# Estimador.net
KiCad netlist of a schematic drawn in Altium Designer
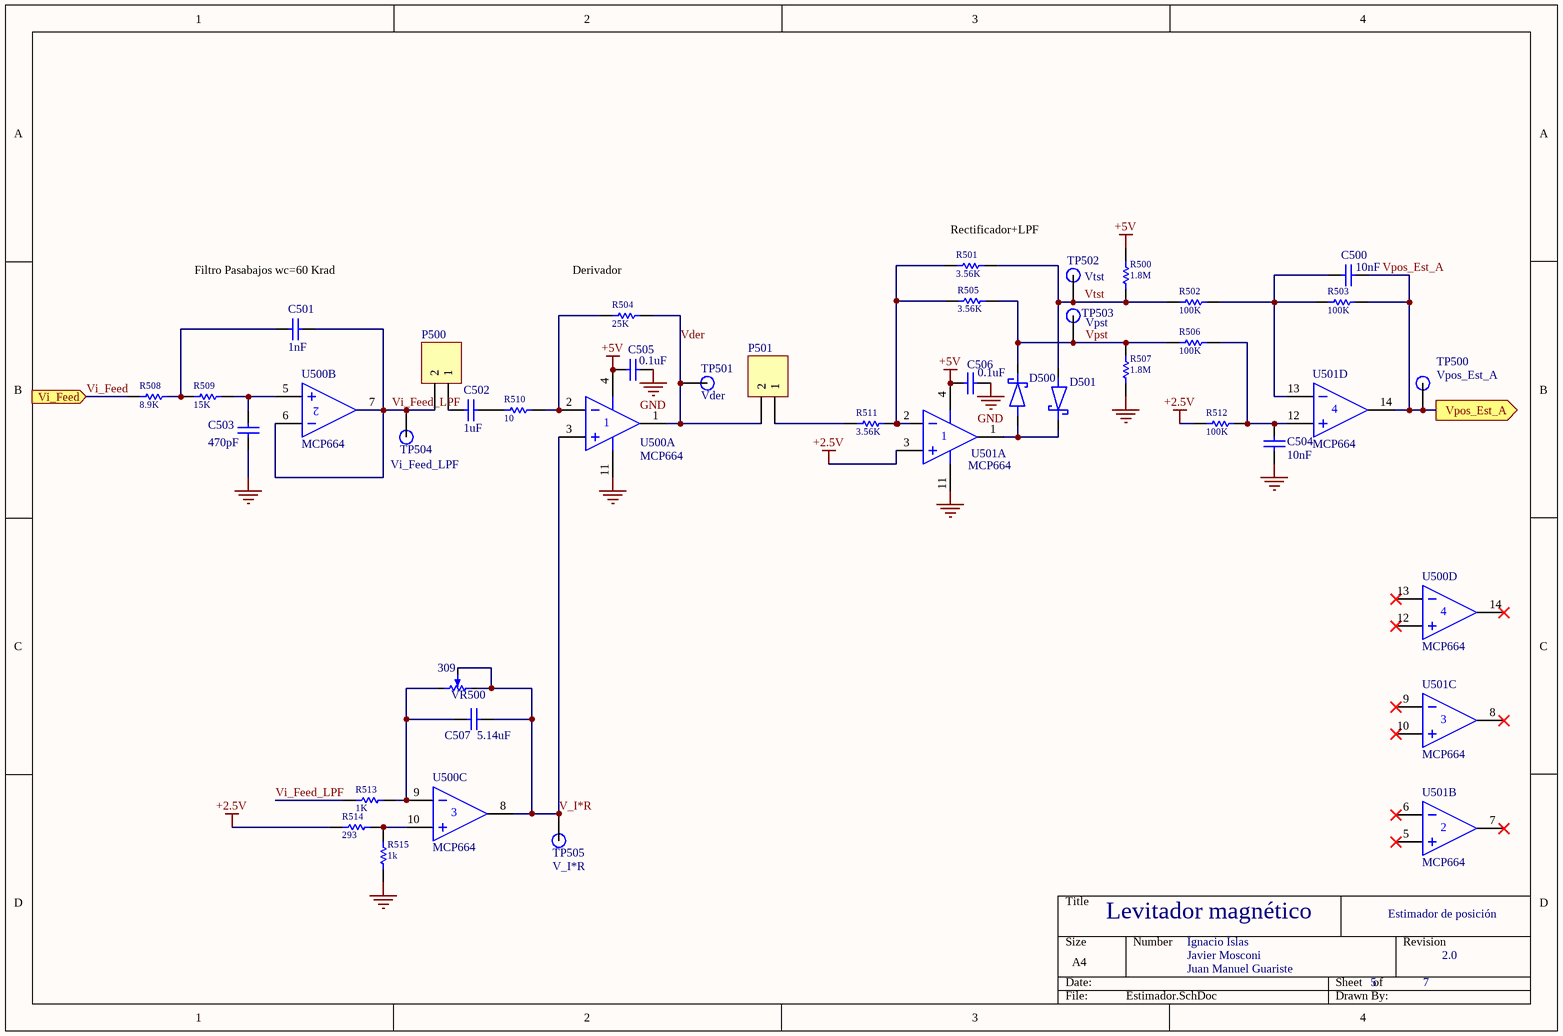
[diagram p0: Estimador.SchDoc]

(export (version "E")
  (design (tool "Eeschema 10.0.6"))
  (components
    (comp (ref "C500")
      (value "10nF")
      (footprint "C1206")
      (description "CAP CER 10000PF 500V X7R 1206")
      (fields (field (name "MANUFACTURER") "KEMET") (field (name "Comment") "Capacitor"))
      (libsource (lib "Levitador_GMI") (part "Capacitor"))
    )
    (comp (ref "C501")
      (value "1nF")
      (footprint "C1206")
      (description "CAP CER 1000PF 2KV X7R 1206")
      (fields (field (name "MANUFACTURER") "Johanson Dielectrics Inc.") (field (name "Comment") "Capacitor"))
      (libsource (lib "Levitador_GMI") (part "Capacitor"))
    )
    (comp (ref "C502")
      (value "1uF")
      (footprint "C1206")
      (description "CAP CER 1UF 25V X7R 1206")
      (fields (field (name "MANUFACTURER") "CAL-CHIP ELECTRONICS, INC.") (field (name "Comment") "Capacitor"))
      (libsource (lib "Levitador_GMI") (part "Capacitor"))
    )
    (comp (ref "C503")
      (value "470pF")
      (footprint "C1206")
      (description "CAP CER 470PF 1KV C0G/NP0 1206")
      (fields (field (name "MANUFACTURER") "Samsung Electro-Mechanics") (field (name "Comment") "Capacitor"))
      (libsource (lib "Levitador_GMI") (part "Capacitor"))
    )
    (comp (ref "C504")
      (value "10nF")
      (footprint "C1206")
      (description "CAP CER 10000PF 500V X7R 1206")
      (fields (field (name "MANUFACTURER") "KEMET") (field (name "Comment") "Capacitor"))
      (libsource (lib "Levitador_GMI") (part "Capacitor"))
    )
    (comp (ref "C505")
      (value "0.1uF")
      (footprint "C1206")
      (description "CAP CER 0.1UF 50V X7R 1206")
      (fields (field (name "MANUFACTURER") "Venkel") (field (name "Comment") "Capacitor"))
      (libsource (lib "Levitador_GMI") (part "Capacitor"))
    )
    (comp (ref "C506")
      (value "0.1uF")
      (footprint "C1206")
      (description "CAP CER 0.1UF 50V X7R 1206")
      (fields (field (name "MANUFACTURER") "Venkel") (field (name "Comment") "Capacitor"))
      (libsource (lib "Levitador_GMI") (part "Capacitor"))
    )
    (comp (ref "C507")
      (value "5.14uF")
      (footprint "C1206")
      (description "CAP CER 5100PF 100V NP0 5% 1206")
      (fields (field (name "MANUFACTURER") "KEMET") (field (name "Comment") "Capacitor"))
      (libsource (lib "Levitador_GMI") (part "Capacitor"))
    )
    (comp (ref "D500")
      (value "RSX205LAM30TR")
      (footprint "SODFL4725X105N")
      (description "DIODE SCHOTTKY 30V 2A PMDTM")
      (fields (field (name "MANUFACTURER") "ROHM Semiconductor"))
      (libsource (lib "Levitador_GMI") (part "RSX205LAM30TR"))
    )
    (comp (ref "D501")
      (value "RSX205LAM30TR")
      (footprint "SODFL4725X105N")
      (description "DIODE SCHOTTKY 30V 2A PMDTM")
      (fields (field (name "MANUFACTURER") "ROHM Semiconductor"))
      (libsource (lib "Levitador_GMI") (part "RSX205LAM30TR"))
    )
    (comp (ref "P500")
      (value "Header 2")
      (footprint "HDR1X2")
      (description "TERM BLK 2P SIDE ENT 2.54MM PCB")
      (fields (field (name "MANUFACTURER") "TE Connectivity AMP Connectors"))
      (libsource (lib "Levitador_GMI") (part "Header 2"))
    )
    (comp (ref "P501")
      (value "Header 2")
      (footprint "HDR1X2")
      (description "TERM BLK 2P SIDE ENT 2.54MM PCB")
      (fields (field (name "MANUFACTURER") "TE Connectivity AMP Connectors"))
      (libsource (lib "Levitador_GMI") (part "Header 2"))
    )
    (comp (ref "R500")
      (value "1.8M")
      (footprint "Levitador_GMI:R1206")
      (description "RES 1.8M OHM 1% 1/4W 1206")
      (fields (field (name "MANUFACTURER") "YAGEO") (field (name "TOLERANCE") "1%"))
      (libsource (lib "Levitador_GMI") (part "R1206"))
    )
    (comp (ref "R501")
      (value "3.56K")
      (footprint "Levitador_GMI:R1206")
      (description "RES 3.57K OHM 1% 1/4W 1206")
      (fields (field (name "MANUFACTURER") "YAGEO") (field (name "TOLERANCE") "1%"))
      (libsource (lib "Levitador_GMI") (part "R1206"))
    )
    (comp (ref "R502")
      (value "100K")
      (footprint "Levitador_GMI:R1206")
      (description "RES 100K OHM 1% 1/4W 1206")
      (fields (field (name "MANUFACTURER") "Stackpole Electronics Inc") (field (name "TOLERANCE") "1%"))
      (libsource (lib "Levitador_GMI") (part "R1206"))
    )
    (comp (ref "R503")
      (value "100K")
      (footprint "Levitador_GMI:R1206")
      (description "RES 100K OHM 1% 1/4W 1206")
      (fields (field (name "MANUFACTURER") "Stackpole Electronics Inc") (field (name "TOLERANCE") "1%"))
      (libsource (lib "Levitador_GMI") (part "R1206"))
    )
    (comp (ref "R504")
      (value "25K")
      (footprint "Levitador_GMI:R1206")
      (description "RES SMD 25K OHM 1% 1/4W 1206")
      (fields
        (field (name "MANUFACTURER") "Vishay Foil Resistors (Division of Vishay Precision Group)")
        (field (name "TOLERANCE") "1%")
      )
      (libsource (lib "Levitador_GMI") (part "R1206"))
    )
    (comp (ref "R505")
      (value "3.56K")
      (footprint "Levitador_GMI:R1206")
      (description "RES 3.57K OHM 1% 1/4W 1206")
      (fields (field (name "MANUFACTURER") "YAGEO") (field (name "TOLERANCE") "1%"))
      (libsource (lib "Levitador_GMI") (part "R1206"))
    )
    (comp (ref "R506")
      (value "100K")
      (footprint "Levitador_GMI:R1206")
      (description "RES 100K OHM 1% 1/4W 1206")
      (fields (field (name "MANUFACTURER") "Stackpole Electronics Inc") (field (name "TOLERANCE") "1%"))
      (libsource (lib "Levitador_GMI") (part "R1206"))
    )
    (comp (ref "R507")
      (value "1.8M")
      (footprint "Levitador_GMI:R1206")
      (description "RES 1.8M OHM 1% 1/4W 1206")
      (fields (field (name "MANUFACTURER") "YAGEO") (field (name "TOLERANCE") "1%"))
      (libsource (lib "Levitador_GMI") (part "R1206"))
    )
    (comp (ref "R508")
      (value "8.9K")
      (footprint "Levitador_GMI:R1206")
      (description "RES 8.87K OHM 1% 1/4W 1206")
      (fields (field (name "MANUFACTURER") "YAGEO") (field (name "TOLERANCE") "1%"))
      (libsource (lib "Levitador_GMI") (part "R1206"))
    )
    (comp (ref "R509")
      (value "15K")
      (footprint "Levitador_GMI:R1206")
      (description "RES 15K OHM 1% 1/4W 1206")
      (fields (field (name "MANUFACTURER") "Vishay Dale") (field (name "TOLERANCE") "1%"))
      (libsource (lib "Levitador_GMI") (part "R1206"))
    )
    (comp (ref "R510")
      (value "10")
      (footprint "Levitador_GMI:R1206")
      (description "RES 10 OHM 1% 1/4W 1206")
      (fields (field (name "MANUFACTURER") "Stackpole Electronics Inc") (field (name "TOLERANCE") "1%"))
      (libsource (lib "Levitador_GMI") (part "R1206"))
    )
    (comp (ref "R511")
      (value "3.56K")
      (footprint "Levitador_GMI:R1206")
      (description "RES 3.57K OHM 1% 1/4W 1206")
      (fields (field (name "MANUFACTURER") "YAGEO") (field (name "TOLERANCE") "1%"))
      (libsource (lib "Levitador_GMI") (part "R1206"))
    )
    (comp (ref "R512")
      (value "100K")
      (footprint "Levitador_GMI:R1206")
      (description "RES 100K OHM 1% 1/4W 1206")
      (fields (field (name "MANUFACTURER") "Stackpole Electronics Inc") (field (name "TOLERANCE") "1%"))
      (libsource (lib "Levitador_GMI") (part "R1206"))
    )
    (comp (ref "R513")
      (value "1K")
      (footprint "Levitador_GMI:R1206")
      (description "RES 1K OHM 1% 1/4W 1206")
      (fields (field (name "MANUFACTURER") "Stackpole Electronics Inc") (field (name "TOLERANCE") "1%"))
      (libsource (lib "Levitador_GMI") (part "R1206"))
    )
    (comp (ref "R514")
      (value "293")
      (footprint "Levitador_GMI:R1206")
      (description "RES SMD 294 OHM 1% 1/4W 1206")
      (fields (field (name "MANUFACTURER") "Vishay Dale") (field (name "TOLERANCE") "1%"))
      (libsource (lib "Levitador_GMI") (part "R1206"))
    )
    (comp (ref "R515")
      (value "1k")
      (footprint "Levitador_GMI:R1206")
      (description "RES 1K OHM 1% 1/4W 1206")
      (fields (field (name "MANUFACTURER") "Stackpole Electronics Inc") (field (name "TOLERANCE") "1%"))
      (libsource (lib "Levitador_GMI") (part "R1206"))
    )
    (comp (ref "TP500")
      (value "Vpos_Est_A")
      (footprint "TestPoint Keystone 5000 Silver-Red")
      (description "PC TEST POINT MINIATURE RED")
      (fields (field (name "MANUFACTURER") "Keystone Electronics"))
      (libsource (lib "Levitador_GMI") (part "Testpoint"))
    )
    (comp (ref "TP501")
      (value "Vder")
      (footprint "TestPoint Keystone 5000 Silver-Red")
      (description "PC TEST POINT MINIATURE RED")
      (fields (field (name "MANUFACTURER") "Keystone Electronics"))
      (libsource (lib "Levitador_GMI") (part "Testpoint"))
    )
    (comp (ref "TP502")
      (value "Vtst")
      (footprint "TestPoint Keystone 5000 Silver-Red")
      (description "PC TEST POINT MINIATURE RED")
      (fields (field (name "MANUFACTURER") "Keystone Electronics"))
      (libsource (lib "Levitador_GMI") (part "Testpoint"))
    )
    (comp (ref "TP503")
      (value "Vpst")
      (footprint "TestPoint Keystone 5000 Silver-Red")
      (description "PC TEST POINT MINIATURE RED")
      (fields (field (name "MANUFACTURER") "Keystone Electronics"))
      (libsource (lib "Levitador_GMI") (part "Testpoint"))
    )
    (comp (ref "TP504")
      (value "Vi_Feed_LPF")
      (footprint "TestPoint Keystone 5000 Silver-Red")
      (description "PC TEST POINT MINIATURE RED")
      (fields (field (name "MANUFACTURER") "Keystone Electronics"))
      (libsource (lib "Levitador_GMI") (part "Testpoint"))
    )
    (comp (ref "TP505")
      (value "V_I*R")
      (footprint "TestPoint Keystone 5000 Silver-Red")
      (description "PC TEST POINT MINIATURE RED")
      (fields (field (name "MANUFACTURER") "Keystone Electronics"))
      (libsource (lib "Levitador_GMI") (part "Testpoint"))
    )
    (comp (ref "U500")
      (value "MCP664")
      (footprint "SOIC14")
      (description "IC OPAMP GP 4 CIRCUIT 14TSSOP")
      (fields (field (name "MANUFACTURER") "Microchip Technology"))
      (libsource (lib "Levitador_GMI") (part "MCP664"))
    )
    (comp (ref "U501")
      (value "MCP664")
      (footprint "SOIC14")
      (description "IC OPAMP GP 4 CIRCUIT 14TSSOP")
      (fields (field (name "MANUFACTURER") "Microchip Technology"))
      (libsource (lib "Levitador_GMI") (part "MCP664"))
    )
    (comp (ref "VR500")
      (value "309")
      (footprint "3299Y1203LF")
      (description "TRIMMER 500 OHM 0.5W PC PIN TOP")
      (fields (field (name "MANUFACTURER") "Bourns Inc.") (field (name "Comment") "Trimmer (Thru-Hole)"))
      (libsource (lib "Levitador_GMI") (part "Trimmer"))
    )
  )
  (nets
    (net (code "1") (name "+2.5V") (class "Default")
      (node (ref "R512") (pin "2") (pinfunction "2_2") (pintype "passive"))
      (node (ref "R514") (pin "1") (pinfunction "1_1") (pintype "passive"))
      (node (ref "U501") (pin "3") (pinfunction "IN+_3") (pintype "passive"))
    )
    (net (code "2") (name "+5V") (class "Default")
      (node (ref "C505") (pin "1") (pinfunction "1_1") (pintype "passive"))
      (node (ref "C506") (pin "1") (pinfunction "1_1") (pintype "passive"))
      (node (ref "R500") (pin "2") (pinfunction "2_2") (pintype "passive"))
      (node (ref "U500") (pin "4") (pinfunction "V+_4") (pintype "power_in"))
      (node (ref "U501") (pin "4") (pinfunction "V+_4") (pintype "power_in"))
    )
    (net (code "3") (name "/V_I*R") (class "Default")
      (node (ref "C507") (pin "1") (pinfunction "1_1") (pintype "passive"))
      (node (ref "TP505") (pin "1") (pinfunction "1_1") (pintype "passive"))
      (node (ref "U500") (pin "3") (pinfunction "IN+_3") (pintype "passive"))
      (node (ref "U500") (pin "8") (pinfunction "OUT_8") (pintype "passive"))
      (node (ref "VR500") (pin "2") (pinfunction "W_2") (pintype "passive"))
      (node (ref "VR500") (pin "3") (pinfunction "CW_3") (pintype "passive"))
    )
    (net (code "4") (name "/Vder") (class "Default")
      (node (ref "P501") (pin "2") (pinfunction "2_2") (pintype "passive"))
      (node (ref "R504") (pin "2") (pinfunction "2_2") (pintype "passive"))
      (node (ref "TP501") (pin "1") (pinfunction "1_1") (pintype "passive"))
      (node (ref "U500") (pin "1") (pinfunction "OUT_1") (pintype "passive"))
    )
    (net (code "5") (name "/Vi_Feed") (class "Default")
      (node (ref "R508") (pin "1") (pinfunction "1_1") (pintype "passive"))
    )
    (net (code "6") (name "/Vi_Feed_LPF") (class "Default")
      (node (ref "C501") (pin "1") (pinfunction "1_1") (pintype "passive"))
      (node (ref "P500") (pin "2") (pinfunction "2_2") (pintype "passive"))
      (node (ref "R513") (pin "1") (pinfunction "1_1") (pintype "passive"))
      (node (ref "TP504") (pin "1") (pinfunction "1_1") (pintype "passive"))
      (node (ref "U500") (pin "6") (pinfunction "IN-_6") (pintype "passive"))
      (node (ref "U500") (pin "7") (pinfunction "OUT_7") (pintype "passive"))
    )
    (net (code "7") (name "/Vpos_Est_A") (class "Default")
      (node (ref "C500") (pin "1") (pinfunction "1_1") (pintype "passive"))
      (node (ref "R503") (pin "1") (pinfunction "1_1") (pintype "passive"))
      (node (ref "TP500") (pin "1") (pinfunction "1_1") (pintype "passive"))
      (node (ref "U501") (pin "14") (pinfunction "OUT_14") (pintype "passive"))
    )
    (net (code "8") (name "/Vpst") (class "Default")
      (node (ref "D500") (pin "1") (pinfunction "K_1") (pintype "passive"))
      (node (ref "R505") (pin "2") (pinfunction "2_2") (pintype "passive"))
      (node (ref "R506") (pin "1") (pinfunction "1_1") (pintype "passive"))
      (node (ref "R507") (pin "2") (pinfunction "2_2") (pintype "passive"))
      (node (ref "TP503") (pin "1") (pinfunction "1_1") (pintype "passive"))
    )
    (net (code "9") (name "/Vtst") (class "Default")
      (node (ref "D501") (pin "2") (pinfunction "A_2") (pintype "passive"))
      (node (ref "R500") (pin "1") (pinfunction "1_1") (pintype "passive"))
      (node (ref "R501") (pin "2") (pinfunction "2_2") (pintype "passive"))
      (node (ref "R502") (pin "1") (pinfunction "1_1") (pintype "passive"))
      (node (ref "TP502") (pin "1") (pinfunction "1_1") (pintype "passive"))
    )
    (net (code "10") (name "GND") (class "Default")
      (node (ref "C503") (pin "2") (pinfunction "2_2") (pintype "passive"))
      (node (ref "C504") (pin "1") (pinfunction "1_1") (pintype "passive"))
      (node (ref "C505") (pin "2") (pinfunction "2_2") (pintype "passive"))
      (node (ref "C506") (pin "2") (pinfunction "2_2") (pintype "passive"))
      (node (ref "R507") (pin "1") (pinfunction "1_1") (pintype "passive"))
      (node (ref "R515") (pin "1") (pinfunction "1_1") (pintype "passive"))
      (node (ref "U500") (pin "11") (pinfunction "V-_11") (pintype "power_in"))
      (node (ref "U501") (pin "11") (pinfunction "V-_11") (pintype "power_in"))
    )
    (net (code "11") (name "Net-(C501-Pad2)") (class "Default")
      (node (ref "C501") (pin "2") (pinfunction "2_2") (pintype "passive"))
      (node (ref "R508") (pin "2") (pinfunction "2_2") (pintype "passive"))
      (node (ref "R509") (pin "1") (pinfunction "1_1") (pintype "passive"))
    )
    (net (code "12") (name "Net-(C502-Pad1)") (class "Default")
      (node (ref "C502") (pin "1") (pinfunction "1_1") (pintype "passive"))
      (node (ref "P500") (pin "1") (pinfunction "1_1") (pintype "passive"))
    )
    (net (code "13") (name "Net-(C502-Pad2)") (class "Default")
      (node (ref "C502") (pin "2") (pinfunction "2_2") (pintype "passive"))
      (node (ref "R510") (pin "1") (pinfunction "1_1") (pintype "passive"))
    )
    (net (code "14") (name "Net-(D500-A)") (class "Default")
      (node (ref "D500") (pin "2") (pinfunction "A_2") (pintype "passive"))
      (node (ref "D501") (pin "1") (pinfunction "K_1") (pintype "passive"))
      (node (ref "U501") (pin "1") (pinfunction "OUT_1") (pintype "passive"))
    )
    (net (code "15") (name "Net-(P501-Pad1)") (class "Default")
      (node (ref "P501") (pin "1") (pinfunction "1_1") (pintype "passive"))
      (node (ref "R511") (pin "1") (pinfunction "1_1") (pintype "passive"))
    )
    (net (code "16") (name "Net-(U500A-IN-)") (class "Default")
      (node (ref "R504") (pin "1") (pinfunction "1_1") (pintype "passive"))
      (node (ref "R510") (pin "2") (pinfunction "2_2") (pintype "passive"))
      (node (ref "U500") (pin "2") (pinfunction "IN-_2") (pintype "passive"))
    )
    (net (code "17") (name "Net-(U500B-IN+)") (class "Default")
      (node (ref "C503") (pin "1") (pinfunction "1_1") (pintype "passive"))
      (node (ref "R509") (pin "2") (pinfunction "2_2") (pintype "passive"))
      (node (ref "U500") (pin "5") (pinfunction "IN+_5") (pintype "passive"))
    )
    (net (code "18") (name "Net-(U500C-IN+)") (class "Default")
      (node (ref "R514") (pin "2") (pinfunction "2_2") (pintype "passive"))
      (node (ref "R515") (pin "2") (pinfunction "2_2") (pintype "passive"))
      (node (ref "U500") (pin "10") (pinfunction "IN+_10") (pintype "passive"))
    )
    (net (code "19") (name "Net-(U500C-IN-)") (class "Default")
      (node (ref "C507") (pin "2") (pinfunction "2_2") (pintype "passive"))
      (node (ref "R513") (pin "2") (pinfunction "2_2") (pintype "passive"))
      (node (ref "U500") (pin "9") (pinfunction "IN-_9") (pintype "passive"))
      (node (ref "VR500") (pin "1") (pinfunction "CCW_1") (pintype "passive"))
    )
    (net (code "20") (name "Net-(U501A-IN-)") (class "Default")
      (node (ref "R501") (pin "1") (pinfunction "1_1") (pintype "passive"))
      (node (ref "R505") (pin "1") (pinfunction "1_1") (pintype "passive"))
      (node (ref "R511") (pin "2") (pinfunction "2_2") (pintype "passive"))
      (node (ref "U501") (pin "2") (pinfunction "IN-_2") (pintype "passive"))
    )
    (net (code "21") (name "Net-(U501D-IN+)") (class "Default")
      (node (ref "C504") (pin "2") (pinfunction "2_2") (pintype "passive"))
      (node (ref "R506") (pin "2") (pinfunction "2_2") (pintype "passive"))
      (node (ref "R512") (pin "1") (pinfunction "1_1") (pintype "passive"))
      (node (ref "U501") (pin "12") (pinfunction "IN+_12") (pintype "passive"))
    )
    (net (code "22") (name "Net-(U501D-IN-)") (class "Default")
      (node (ref "C500") (pin "2") (pinfunction "2_2") (pintype "passive"))
      (node (ref "R502") (pin "2") (pinfunction "2_2") (pintype "passive"))
      (node (ref "R503") (pin "2") (pinfunction "2_2") (pintype "passive"))
      (node (ref "U501") (pin "13") (pinfunction "IN-_13") (pintype "passive"))
    )
    (net (code "23") (name "unconnected-(U500D-IN+-Pad12)") (class "Default")
      (node (ref "U500") (pin "12") (pinfunction "IN+_12") (pintype "passive+no_connect"))
    )
    (net (code "24") (name "unconnected-(U500D-IN--Pad13)") (class "Default")
      (node (ref "U500") (pin "13") (pinfunction "IN-_13") (pintype "passive+no_connect"))
    )
    (net (code "25") (name "unconnected-(U500D-OUT-Pad14)") (class "Default")
      (node (ref "U500") (pin "14") (pinfunction "OUT_14") (pintype "passive+no_connect"))
    )
    (net (code "26") (name "unconnected-(U501B-IN+-Pad5)") (class "Default")
      (node (ref "U501") (pin "5") (pinfunction "IN+_5") (pintype "passive+no_connect"))
    )
    (net (code "27") (name "unconnected-(U501B-IN--Pad6)") (class "Default")
      (node (ref "U501") (pin "6") (pinfunction "IN-_6") (pintype "passive+no_connect"))
    )
    (net (code "28") (name "unconnected-(U501B-OUT-Pad7)") (class "Default")
      (node (ref "U501") (pin "7") (pinfunction "OUT_7") (pintype "passive+no_connect"))
    )
    (net (code "29") (name "unconnected-(U501C-IN+-Pad10)") (class "Default")
      (node (ref "U501") (pin "10") (pinfunction "IN+_10") (pintype "passive+no_connect"))
    )
    (net (code "30") (name "unconnected-(U501C-IN--Pad9)") (class "Default")
      (node (ref "U501") (pin "9") (pinfunction "IN-_9") (pintype "passive+no_connect"))
    )
    (net (code "31") (name "unconnected-(U501C-OUT-Pad8)") (class "Default")
      (node (ref "U501") (pin "8") (pinfunction "OUT_8") (pintype "passive+no_connect"))
    )
  )
)
